# PPGShieldSmall-V0_2_1.net
KiCad netlist of a schematic drawn in EAGLE
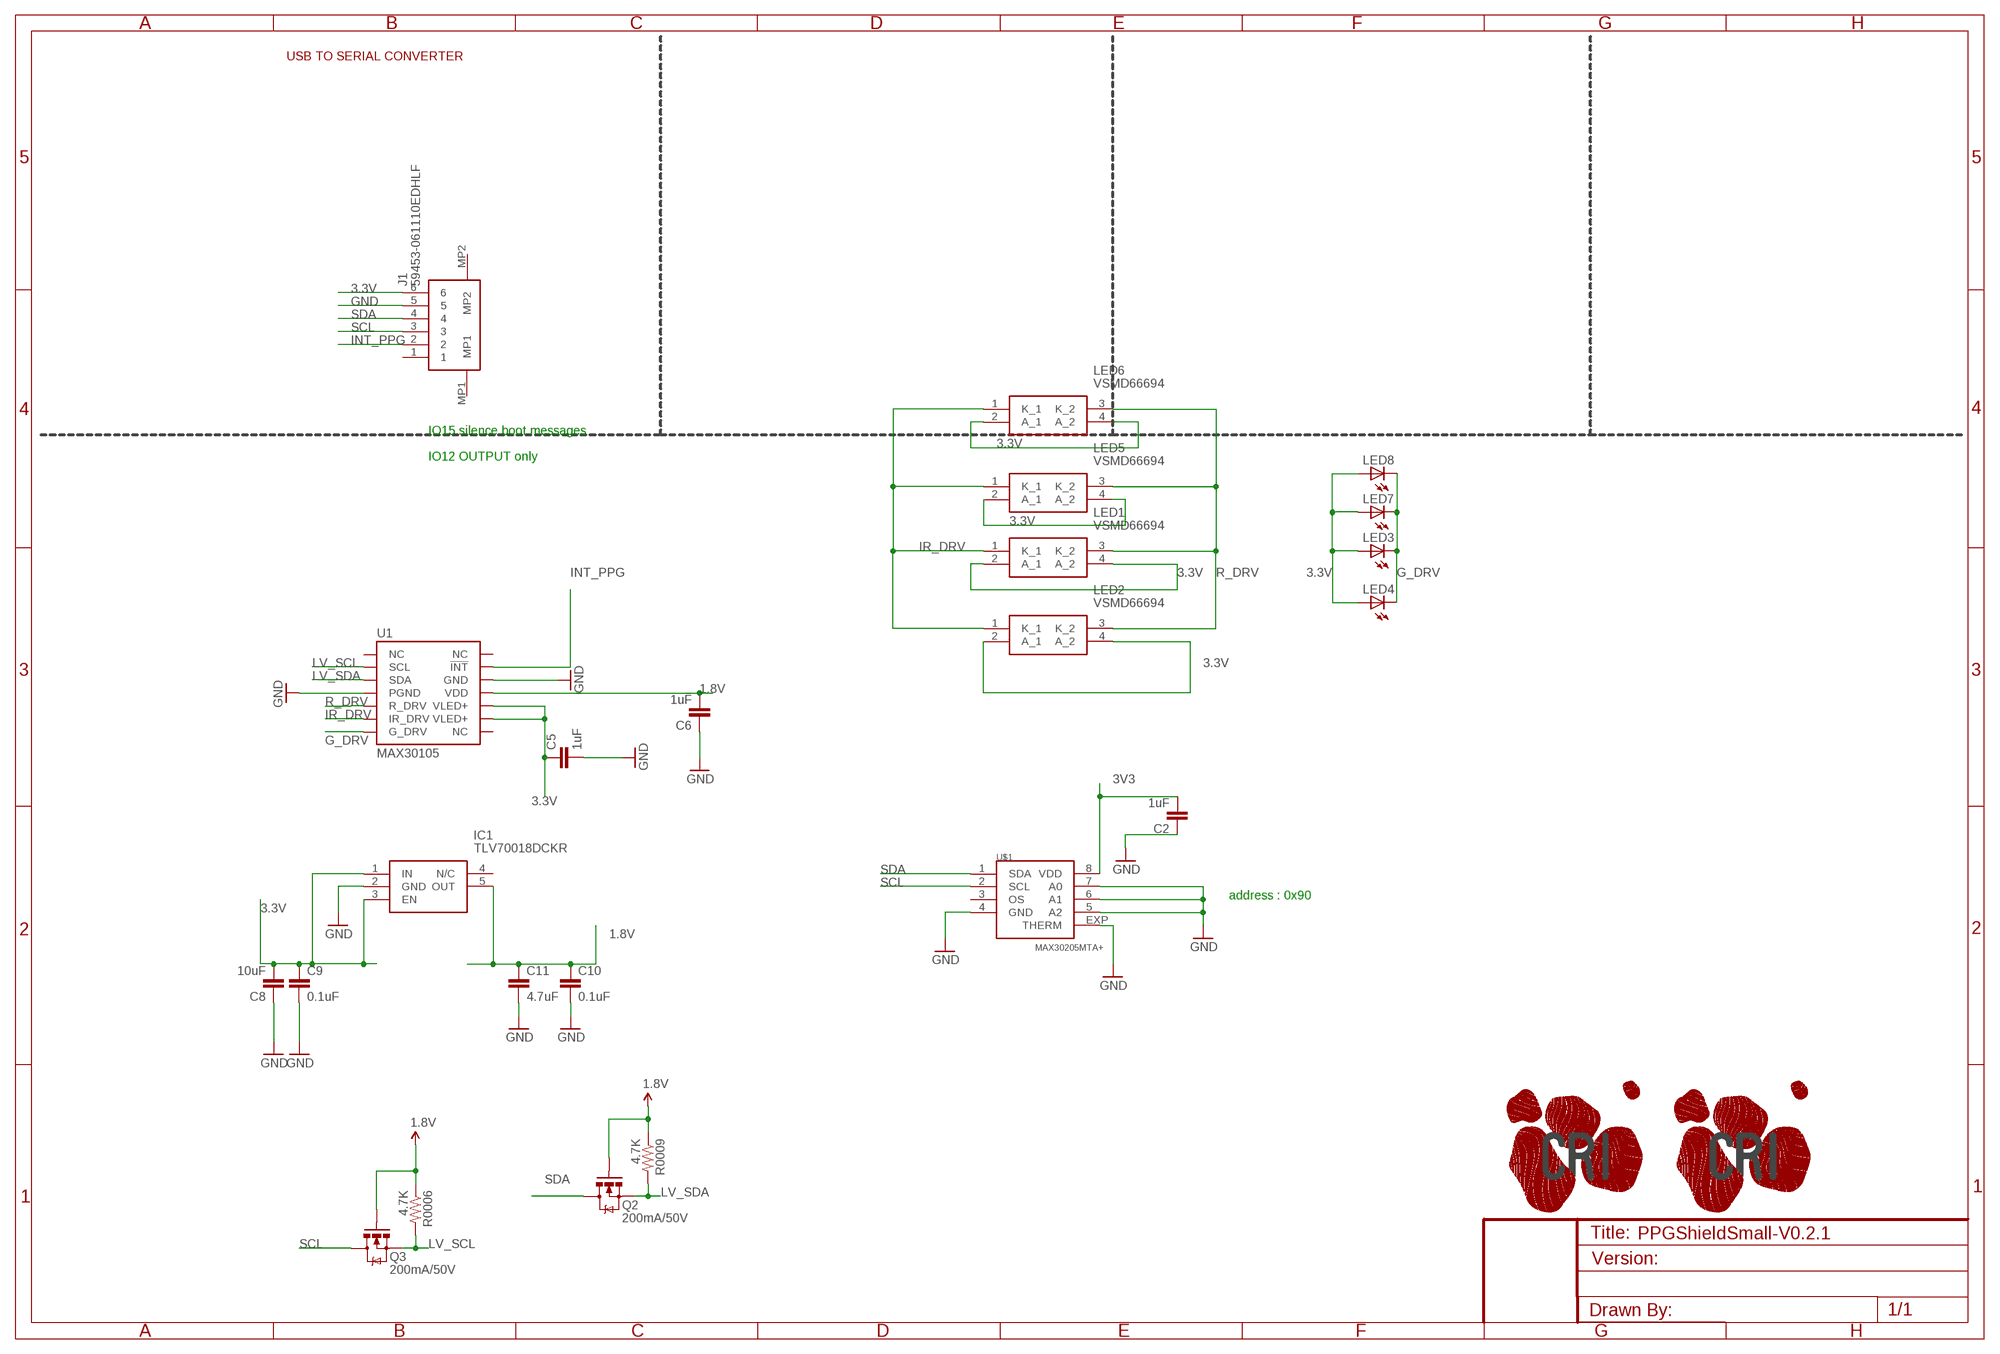
[diagram p0: schematic, sheet 1]

(export (version "E")
  (design (tool "Eeschema 10.0.6"))
  (components
    (comp (ref "C2")
      (value "1uF")
      (footprint "eagle-import:0402-CAP")
      (fields
        (field (name "MF") "Murata Electronics")
        (field (name "MPN") "GRM155R61A105KE15D")
        (field (name "TOLERANCE") "10%")
      )
      (libsource (lib "eagle-import") (part "CAP0402-1UF"))
    )
    (comp (ref "C5")
      (value "1uF")
      (footprint "eagle-import:0402-CAP")
      (fields
        (field (name "MF") "Murata Electronics")
        (field (name "MPN") "GRM155R61A105KE15D")
        (field (name "TOLERANCE") "10%")
      )
      (libsource (lib "eagle-import") (part "CAP0402-1UF"))
    )
    (comp (ref "C6")
      (value "1uF")
      (footprint "eagle-import:0402-CAP")
      (fields
        (field (name "MF") "Murata Electronics")
        (field (name "MPN") "GRM155R61A105KE15D")
        (field (name "TOLERANCE") "10%")
      )
      (libsource (lib "eagle-import") (part "CAP0402-1UF"))
    )
    (comp (ref "C8")
      (value "10uF")
      (footprint "eagle-import:0402-RES")
      (fields
        (field (name "MF") "Murata Electronics")
        (field (name "TOLERANCE") "20%")
        (field (name "VOLTAGE") "6.3V")
      )
      (libsource (lib "eagle-import") (part "CAP0402-10UF-MURATA"))
    )
    (comp (ref "C9")
      (value "0.1uF")
      (footprint "eagle-import:0402-CAP")
      (fields
        (field (name "MF") "Murata Electronics")
        (field (name "MPN") "GRM155R61C104KA88D")
        (field (name "TOLERANCE") "10%")
      )
      (libsource (lib "eagle-import") (part "CAP0402-0.1UF"))
    )
    (comp (ref "C10")
      (value "0.1uF")
      (footprint "eagle-import:0402-CAP")
      (fields
        (field (name "MF") "Murata Electronics")
        (field (name "MPN") "GRM155R61C104KA88D")
        (field (name "TOLERANCE") "10%")
      )
      (libsource (lib "eagle-import") (part "CAP0402-0.1UF"))
    )
    (comp (ref "C11")
      (value "4.7uF")
      (footprint "eagle-import:0402-CAP")
      (fields
        (field (name "MF") "Murata Electronics")
        (field (name "MPN") "GRM155R61C104KA88D")
        (field (name "TOLERANCE") "10%")
      )
      (libsource (lib "eagle-import") (part "CAP0402-0.1UF"))
    )
    (comp (ref "IC1")
      (value "TLV70018DCKR")
      (footprint "eagle-import:SOT65P210X110-5N")
      (fields (field (name "MOUSER_PART_NUMBER") "595-TLV70018DCKR"))
      (libsource (lib "eagle-import") (part "TLV70018DCKR"))
    )
    (comp (ref "J1")
      (value "59453-061110EDHLF")
      (footprint "eagle-import:59453061110EDHLF")
      (libsource (lib "eagle-import") (part "59453-061110EDHLF"))
    )
    (comp (ref "LED1")
      (value "VSMD66694")
      (footprint "eagle-import:VSMD66694")
      (fields (field (name "MOUSER_PART_NUMBER") "78-VSMD66694"))
      (libsource (lib "eagle-import") (part "VSMD66694"))
    )
    (comp (ref "LED2")
      (value "VSMD66694")
      (footprint "eagle-import:VSMD66694")
      (fields (field (name "MOUSER_PART_NUMBER") "78-VSMD66694"))
      (libsource (lib "eagle-import") (part "VSMD66694"))
    )
    (comp (ref "LED3")
      (value "LED0603")
      (footprint "eagle-import:LED-0603")
      (libsource (lib "eagle-import") (part "LED0603"))
    )
    (comp (ref "LED4")
      (value "LED0603")
      (footprint "eagle-import:LED-0603")
      (libsource (lib "eagle-import") (part "LED0603"))
    )
    (comp (ref "LED5")
      (value "VSMD66694")
      (footprint "eagle-import:VSMD66694")
      (fields (field (name "MOUSER_PART_NUMBER") "78-VSMD66694"))
      (libsource (lib "eagle-import") (part "VSMD66694"))
    )
    (comp (ref "LED6")
      (value "VSMD66694")
      (footprint "eagle-import:VSMD66694")
      (fields (field (name "MOUSER_PART_NUMBER") "78-VSMD66694"))
      (libsource (lib "eagle-import") (part "VSMD66694"))
    )
    (comp (ref "LED7")
      (value "LED0603")
      (footprint "eagle-import:LED-0603")
      (libsource (lib "eagle-import") (part "LED0603"))
    )
    (comp (ref "LED8")
      (value "LED0603")
      (footprint "eagle-import:LED-0603")
      (libsource (lib "eagle-import") (part "LED0603"))
    )
    (comp (ref "Q2")
      (value "200mA/50V")
      (footprint "eagle-import:SOT23-3")
      (libsource (lib "eagle-import") (part "MOSFET-NCHANNELBSS138"))
    )
    (comp (ref "Q3")
      (value "200mA/50V")
      (footprint "eagle-import:SOT23-3")
      (libsource (lib "eagle-import") (part "MOSFET-NCHANNELBSS138"))
    )
    (comp (ref "R0006")
      (value "4.7K")
      (footprint "eagle-import:0402-RES")
      (fields
        (field (name "MF") "TE Connectivity")
        (field (name "MPN") "CRG0402F4K7 ")
        (field (name "TOLERANCE") "1%")
      )
      (libsource (lib "eagle-import") (part "RESISTOR0402-4K7"))
    )
    (comp (ref "R0009")
      (value "4.7K")
      (footprint "eagle-import:0402-RES")
      (fields
        (field (name "MF") "TE Connectivity")
        (field (name "MPN") "CRG0402F4K7 ")
        (field (name "TOLERANCE") "1%")
      )
      (libsource (lib "eagle-import") (part "RESISTOR0402-4K7"))
    )
    (comp (ref "U$1")
      (value "MAX30205MTA+")
      (footprint "eagle-import:TDFN-08")
      (libsource (lib "eagle-import") (part "MAX30205MTA+"))
    )
    (comp (ref "U$3")
      (value "LOGO-CRI-NEW-110MM-BOTTOM-SILK")
      (footprint "eagle-import:LOGO_CRI-NEW-BMP10MM-BOTTOM")
      (libsource (lib "eagle-import") (part "LOGO-CRI-NEW-110MM-BOTTOM-SILK"))
    )
    (comp (ref "U$4")
      (value "LOGO-CRI-NEW-110MM-BOTTOM-SILK")
      (footprint "eagle-import:LOGO_CRI-NEW-BMP10MM-BOTTOM")
      (libsource (lib "eagle-import") (part "LOGO-CRI-NEW-110MM-BOTTOM-SILK"))
    )
    (comp (ref "U1")
      (value "MAX30105")
      (footprint "eagle-import:OLGA-14")
      (libsource (lib "eagle-import") (part "MAX30105SMD"))
    )
  )
  (nets
    (net (code "1") (name "/3.3V") (class "Default")
      (node (ref "C5") (pin "1") (pinfunction "1_1") (pintype "passive"))
      (node (ref "C8") (pin "2") (pinfunction "2_2") (pintype "passive"))
      (node (ref "C9") (pin "1") (pinfunction "1_1") (pintype "passive"))
      (node (ref "IC1") (pin "1") (pinfunction "IN_1") (pintype "bidirectional"))
      (node (ref "IC1") (pin "3") (pinfunction "EN_3") (pintype "bidirectional"))
      (node (ref "J1") (pin "6") (pinfunction "6_6") (pintype "bidirectional"))
      (node (ref "LED1") (pin "2") (pinfunction "A_1_2") (pintype "bidirectional"))
      (node (ref "LED1") (pin "4") (pinfunction "A_2_4") (pintype "bidirectional"))
      (node (ref "LED2") (pin "2") (pinfunction "A_1_2") (pintype "bidirectional"))
      (node (ref "LED2") (pin "4") (pinfunction "A_2_4") (pintype "bidirectional"))
      (node (ref "LED3") (pin "A") (pinfunction "A_A") (pintype "passive"))
      (node (ref "LED4") (pin "A") (pinfunction "A_A") (pintype "passive"))
      (node (ref "LED5") (pin "2") (pinfunction "A_1_2") (pintype "bidirectional"))
      (node (ref "LED5") (pin "4") (pinfunction "A_2_4") (pintype "bidirectional"))
      (node (ref "LED6") (pin "2") (pinfunction "A_1_2") (pintype "bidirectional"))
      (node (ref "LED6") (pin "4") (pinfunction "A_2_4") (pintype "bidirectional"))
      (node (ref "LED7") (pin "A") (pinfunction "A_A") (pintype "passive"))
      (node (ref "LED8") (pin "A") (pinfunction "A_A") (pintype "passive"))
      (node (ref "U1") (pin "10") (pinfunction "VLED+_10") (pintype "bidirectional"))
      (node (ref "U1") (pin "9") (pinfunction "VLED+_9") (pintype "bidirectional"))
    )
    (net (code "2") (name "/3V3") (class "Default")
      (node (ref "C2") (pin "2") (pinfunction "2_2") (pintype "passive"))
      (node (ref "U$1") (pin "8") (pinfunction "VDD_8") (pintype "bidirectional"))
    )
    (net (code "3") (name "/G_DRV") (class "Default")
      (node (ref "LED3") (pin "C") (pinfunction "C_C") (pintype "passive"))
      (node (ref "LED4") (pin "C") (pinfunction "C_C") (pintype "passive"))
      (node (ref "LED7") (pin "C") (pinfunction "C_C") (pintype "passive"))
      (node (ref "LED8") (pin "C") (pinfunction "C_C") (pintype "passive"))
      (node (ref "U1") (pin "7") (pinfunction "G_DRV_7") (pintype "bidirectional"))
    )
    (net (code "4") (name "/INT_PPG") (class "Default")
      (node (ref "J1") (pin "2") (pinfunction "2_2") (pintype "bidirectional"))
      (node (ref "U1") (pin "13") (pinfunction "~{INT}_13") (pintype "bidirectional"))
    )
    (net (code "5") (name "/IR_DRV") (class "Default")
      (node (ref "LED1") (pin "1") (pinfunction "K_1_1") (pintype "bidirectional"))
      (node (ref "LED2") (pin "1") (pinfunction "K_1_1") (pintype "bidirectional"))
      (node (ref "LED5") (pin "1") (pinfunction "K_1_1") (pintype "bidirectional"))
      (node (ref "LED6") (pin "1") (pinfunction "K_1_1") (pintype "bidirectional"))
      (node (ref "U1") (pin "6") (pinfunction "IR_DRV_6") (pintype "bidirectional"))
    )
    (net (code "6") (name "/LV_SCL") (class "Default")
      (node (ref "Q3") (pin "2") (pinfunction "S_2") (pintype "passive"))
      (node (ref "R0006") (pin "2") (pinfunction "2_2") (pintype "passive"))
      (node (ref "U1") (pin "2") (pinfunction "SCL_2") (pintype "bidirectional"))
    )
    (net (code "7") (name "/LV_SDA") (class "Default")
      (node (ref "Q2") (pin "2") (pinfunction "S_2") (pintype "passive"))
      (node (ref "R0009") (pin "2") (pinfunction "2_2") (pintype "passive"))
      (node (ref "U1") (pin "3") (pinfunction "SDA_3") (pintype "bidirectional"))
    )
    (net (code "8") (name "/R_DRV") (class "Default")
      (node (ref "LED1") (pin "3") (pinfunction "K_2_3") (pintype "bidirectional"))
      (node (ref "LED2") (pin "3") (pinfunction "K_2_3") (pintype "bidirectional"))
      (node (ref "LED5") (pin "3") (pinfunction "K_2_3") (pintype "bidirectional"))
      (node (ref "LED6") (pin "3") (pinfunction "K_2_3") (pintype "bidirectional"))
      (node (ref "U1") (pin "5") (pinfunction "R_DRV_5") (pintype "bidirectional"))
    )
    (net (code "9") (name "/SCL") (class "Default")
      (node (ref "J1") (pin "3") (pinfunction "3_3") (pintype "bidirectional"))
      (node (ref "Q3") (pin "3") (pinfunction "D_3") (pintype "passive"))
      (node (ref "U$1") (pin "2") (pinfunction "SCL_2") (pintype "bidirectional"))
    )
    (net (code "10") (name "/SDA") (class "Default")
      (node (ref "J1") (pin "4") (pinfunction "4_4") (pintype "bidirectional"))
      (node (ref "Q2") (pin "3") (pinfunction "D_3") (pintype "passive"))
      (node (ref "U$1") (pin "1") (pinfunction "SDA_1") (pintype "bidirectional"))
    )
    (net (code "11") (name "1.8V") (class "Default")
      (node (ref "C10") (pin "1") (pinfunction "1_1") (pintype "passive"))
      (node (ref "C11") (pin "1") (pinfunction "1_1") (pintype "passive"))
      (node (ref "C6") (pin "2") (pinfunction "2_2") (pintype "passive"))
      (node (ref "IC1") (pin "5") (pinfunction "OUT_5") (pintype "bidirectional"))
      (node (ref "Q2") (pin "1") (pinfunction "G_1") (pintype "passive"))
      (node (ref "Q3") (pin "1") (pinfunction "G_1") (pintype "passive"))
      (node (ref "R0006") (pin "1") (pinfunction "1_1") (pintype "passive"))
      (node (ref "R0009") (pin "1") (pinfunction "1_1") (pintype "passive"))
      (node (ref "U1") (pin "11") (pinfunction "VDD_11") (pintype "bidirectional"))
    )
    (net (code "12") (name "GND") (class "Default")
      (node (ref "C10") (pin "2") (pinfunction "2_2") (pintype "passive"))
      (node (ref "C11") (pin "2") (pinfunction "2_2") (pintype "passive"))
      (node (ref "C2") (pin "1") (pinfunction "1_1") (pintype "passive"))
      (node (ref "C5") (pin "2") (pinfunction "2_2") (pintype "passive"))
      (node (ref "C6") (pin "1") (pinfunction "1_1") (pintype "passive"))
      (node (ref "C8") (pin "1") (pinfunction "1_1") (pintype "passive"))
      (node (ref "C9") (pin "2") (pinfunction "2_2") (pintype "passive"))
      (node (ref "IC1") (pin "2") (pinfunction "GND_2") (pintype "bidirectional"))
      (node (ref "J1") (pin "5") (pinfunction "5_5") (pintype "bidirectional"))
      (node (ref "U$1") (pin "4") (pinfunction "GND_4") (pintype "bidirectional"))
      (node (ref "U$1") (pin "5") (pinfunction "A2_5") (pintype "bidirectional"))
      (node (ref "U$1") (pin "6") (pinfunction "A1_6") (pintype "bidirectional"))
      (node (ref "U$1") (pin "7") (pinfunction "A0_7") (pintype "bidirectional"))
      (node (ref "U$1") (pin "EXP") (pinfunction "THERM_EXP") (pintype "bidirectional"))
      (node (ref "U1") (pin "12") (pinfunction "GND_12") (pintype "bidirectional"))
      (node (ref "U1") (pin "4") (pinfunction "PGND_4") (pintype "bidirectional"))
    )
    (net (code "13") (name "unconnected-(IC1-N{slash}C-Pad4)") (class "Default")
      (node (ref "IC1") (pin "4") (pinfunction "N/C_4") (pintype "no_connect"))
    )
    (net (code "14") (name "unconnected-(J1-Pad1)") (class "Default")
      (node (ref "J1") (pin "1") (pinfunction "1_1") (pintype "bidirectional"))
    )
    (net (code "15") (name "unconnected-(J1-PadMP1)") (class "Default")
      (node (ref "J1") (pin "MP1") (pinfunction "MP1_MP1") (pintype "bidirectional"))
    )
    (net (code "16") (name "unconnected-(J1-PadMP2)") (class "Default")
      (node (ref "J1") (pin "MP2") (pinfunction "MP2_MP2") (pintype "bidirectional"))
    )
    (net (code "17") (name "unconnected-(U$1-OS-Pad3)") (class "Default")
      (node (ref "U$1") (pin "3") (pinfunction "OS_3") (pintype "bidirectional"))
    )
    (net (code "18") (name "unconnected-(U1-NC-Pad1)") (class "Default")
      (node (ref "U1") (pin "1") (pinfunction "NC_1") (pintype "bidirectional"))
    )
    (net (code "19") (name "unconnected-(U1-NC-Pad8)") (class "Default")
      (node (ref "U1") (pin "8") (pinfunction "NC_8") (pintype "bidirectional"))
    )
    (net (code "20") (name "unconnected-(U1-NC-Pad14)") (class "Default")
      (node (ref "U1") (pin "14") (pinfunction "NC_14") (pintype "bidirectional"))
    )
  )
)
